# PD_MK2_Connectors.net
KiCad netlist of a schematic drawn in Altium Designer
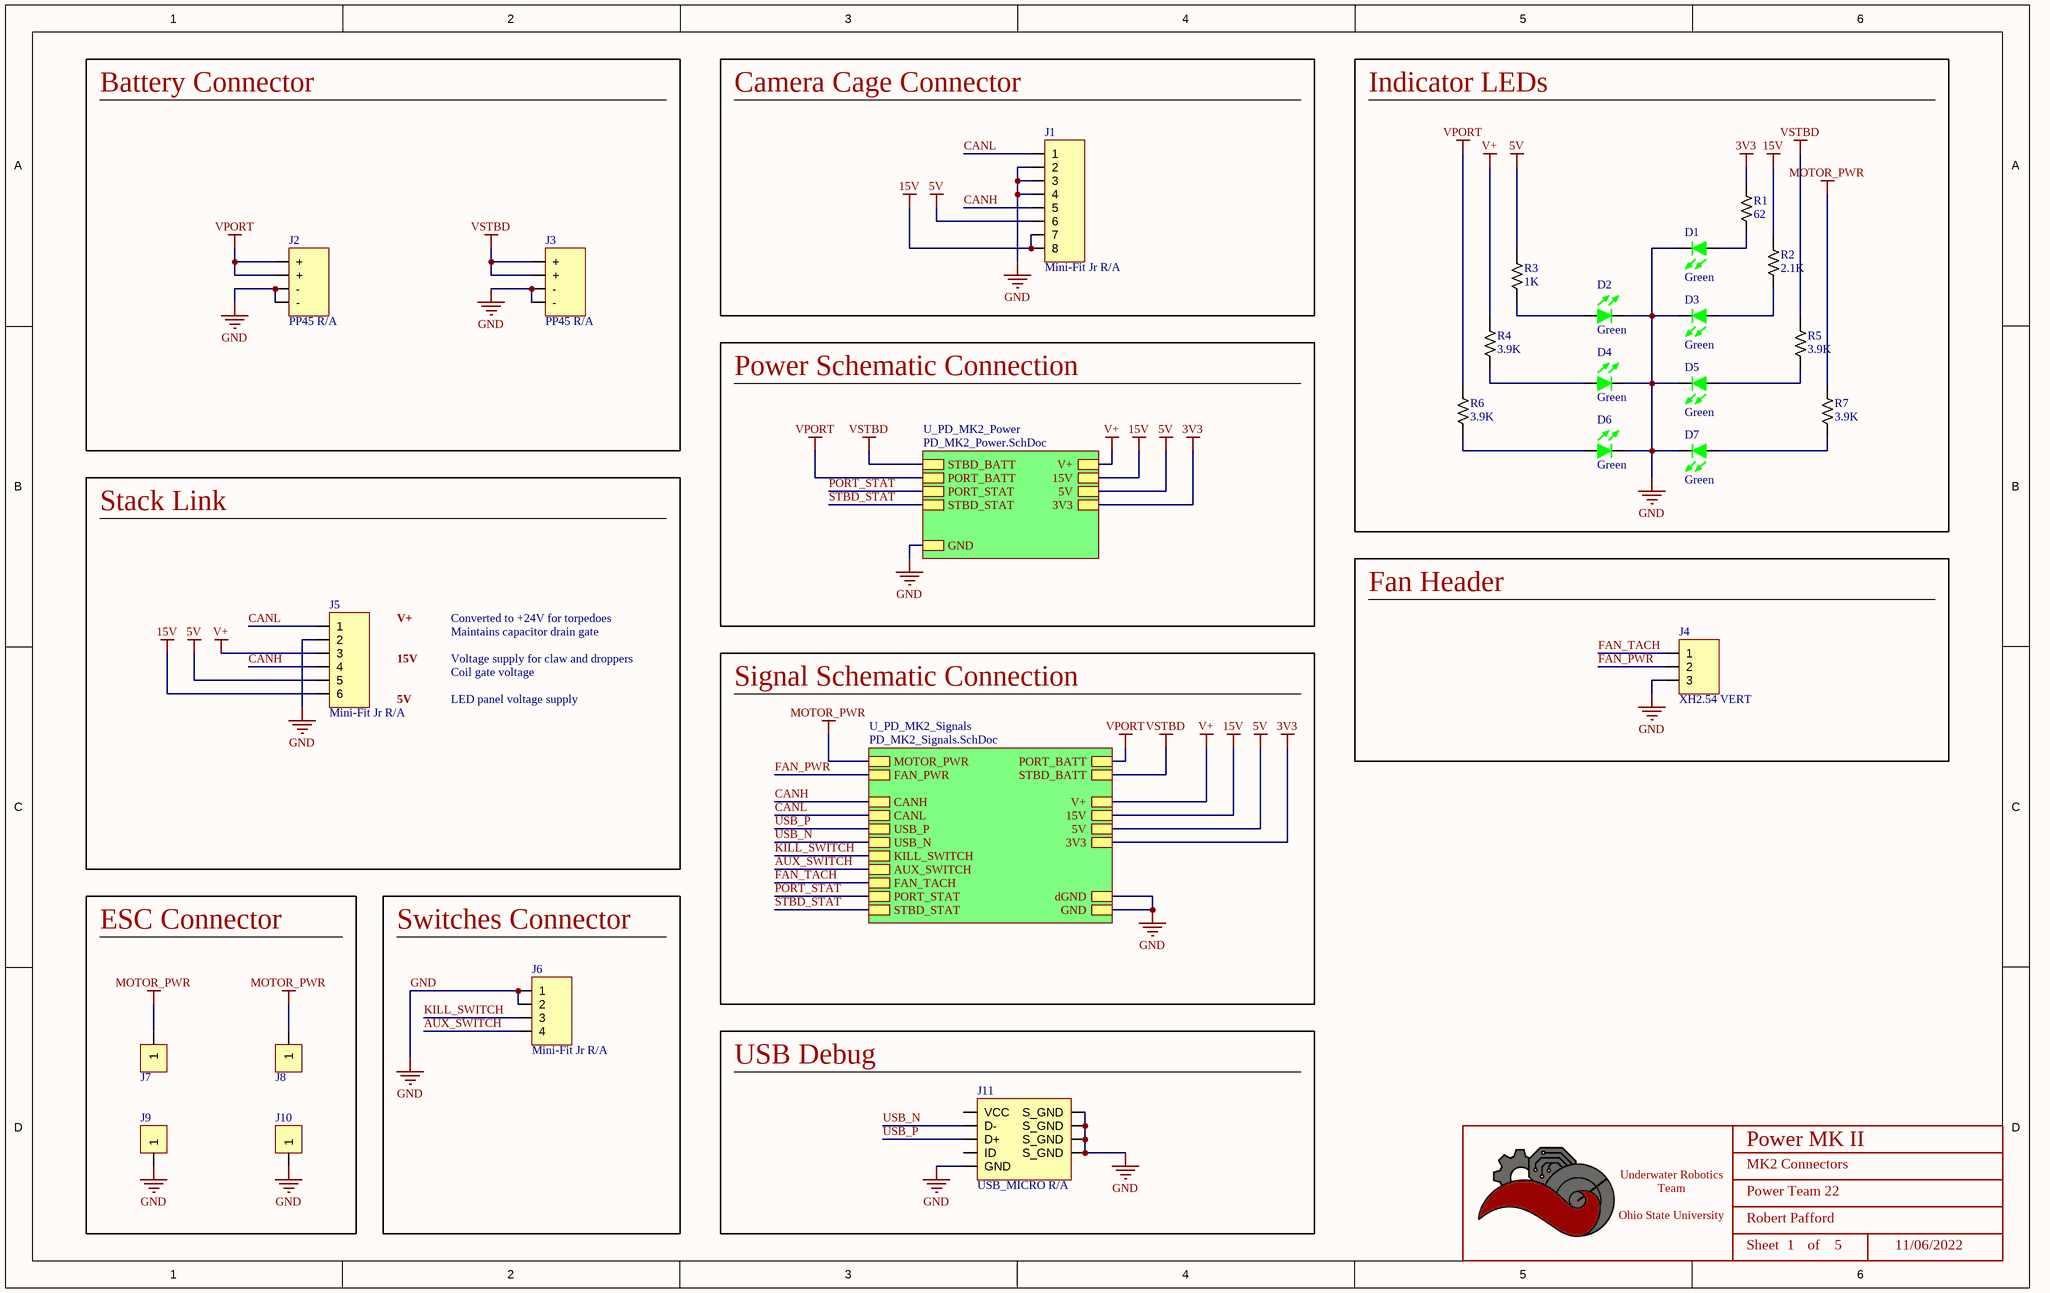
[diagram p0: PD_MK2_Connectors.SchDoc]

(export (version "E")
  (design (tool "Eeschema 10.0.6"))
  (components
    (comp (ref "D1")
      (value "IN-S63AT5G")
      (footprint "LED_0603")
      (description "LED Green Vf= 3V If = 0.005A\r\nIN-S63AT5G")
      (fields (field (name "COLOR") "Green") (field (name "MADE BY") "Robert Pafford"))
      (libsource (lib "Diodes") (part "LED_Green_0603_3V"))
    )
    (comp (ref "D2")
      (value "IN-S63AT5G")
      (footprint "LED_0603")
      (description "LED Green Vf= 3V If = 0.005A\r\nIN-S63AT5G")
      (fields (field (name "COLOR") "Green") (field (name "MADE BY") "Robert Pafford"))
      (libsource (lib "Diodes") (part "LED_Green_0603_3V"))
    )
    (comp (ref "D3")
      (value "IN-S63AT5G")
      (footprint "LED_0603")
      (description "LED Green Vf= 3V If = 0.005A\r\nIN-S63AT5G")
      (fields (field (name "COLOR") "Green") (field (name "MADE BY") "Robert Pafford"))
      (libsource (lib "Diodes") (part "LED_Green_0603_3V"))
    )
    (comp (ref "D4")
      (value "IN-S63AT5G")
      (footprint "LED_0603")
      (description "LED Green Vf= 3V If = 0.005A\r\nIN-S63AT5G")
      (fields (field (name "COLOR") "Green") (field (name "MADE BY") "Robert Pafford"))
      (libsource (lib "Diodes") (part "LED_Green_0603_3V"))
    )
    (comp (ref "D5")
      (value "IN-S63AT5G")
      (footprint "LED_0603")
      (description "LED Green Vf= 3V If = 0.005A\r\nIN-S63AT5G")
      (fields (field (name "COLOR") "Green") (field (name "MADE BY") "Robert Pafford"))
      (libsource (lib "Diodes") (part "LED_Green_0603_3V"))
    )
    (comp (ref "D6")
      (value "IN-S63AT5G")
      (footprint "LED_0603")
      (description "LED Green Vf= 3V If = 0.005A\r\nIN-S63AT5G")
      (fields (field (name "COLOR") "Green") (field (name "MADE BY") "Robert Pafford"))
      (libsource (lib "Diodes") (part "LED_Green_0603_3V"))
    )
    (comp (ref "D7")
      (value "IN-S63AT5G")
      (footprint "LED_0603")
      (description "LED Green Vf= 3V If = 0.005A\r\nIN-S63AT5G")
      (fields (field (name "COLOR") "Green") (field (name "MADE BY") "Robert Pafford"))
      (libsource (lib "Diodes") (part "LED_Green_0603_3V"))
    )
    (comp (ref "J1")
      (value "Mini-Fit Jr R/A")
      (footprint "CONN_MOLEX_MINIFIT JR_8 POS_R/A")
      (description "Molex Minifit Jr. 5569 \r\n8 Pos R/A Natural")
      (fields (field (name "MANUFACTURER") "Molex") (field (name "CREATED BY") "Flip B"))
      (libsource (lib "Connectors") (part "CONN_MOLEX_MINIFIT JR_8POS_R/A"))
    )
    (comp (ref "J2")
      (value "PP45 R/A")
      (footprint "CONN_ANDERSON_PP45_4 POS_R/A")
      (description "Anderson PP45\r\n4 Pos R/A Red/Black")
      (fields (field (name "MANUFACTURER") "Anderson") (field (name "CREATED BY") "Flip B"))
      (libsource (lib "Connectors") (part "CONN_ANDERSON_2x2_R/A"))
    )
    (comp (ref "J3")
      (value "PP45 R/A")
      (footprint "CONN_ANDERSON_PP45_4 POS_R/A")
      (description "Anderson PP45\r\n4 Pos R/A Red/Black")
      (fields (field (name "MANUFACTURER") "Anderson") (field (name "CREATED BY") "Flip B"))
      (libsource (lib "Connectors") (part "CONN_ANDERSON_2x2_R/A"))
    )
    (comp (ref "J4")
      (value "XH2.54 VERT")
      (footprint "CONN_JST_XH254_3POS_VERT")
      (description "JST XH 2.54mm Pitch 3 Pos Vertical")
      (fields (field (name "MANUFACTURER") "JST") (field (name "CREATED BY") "Robert P"))
      (libsource (lib "Connectors") (part "CONN_JST_XH254_3POS_VERT"))
    )
    (comp (ref "J5")
      (value "Mini-Fit Jr R/A")
      (footprint "CONN_MOLEX_MINIFIT JR_6 POS_R/A")
      (description "Molex Minifit Jr. 5569 \r\n6 Pos R/A Natural")
      (fields (field (name "MANUFACTURER") "Molex") (field (name "CREATED BY") "Flip B"))
      (libsource (lib "Connectors") (part "CONN_MOLEX_MINIFIT JR_6POS_R/A"))
    )
    (comp (ref "J6")
      (value "Mini-Fit Jr R/A")
      (footprint "CONN_MOLEX_MINIFIT JR_4 POS_R/A")
      (description "Molex Minifit Jr. 5569 \r\n4 Pos R/A Natural")
      (fields (field (name "MANUFACTURER") "Molex") (field (name "CREATED BY") "Flip B"))
      (libsource (lib "Connectors") (part "CONN_MOLEX_MINIFIT JR_4POS_R/A"))
    )
    (comp (ref "J7")
      (value "Redcube M4 Term 85A")
      (footprint "Redcube M4 Term 85A")
      (fields (field (name "CREATED BY") "Nahtan Ayer"))
      (libsource (lib "Connectors") (part "Redcube M4 Term 85A"))
    )
    (comp (ref "J8")
      (value "Redcube M4 Term 85A")
      (footprint "Redcube M4 Term 85A")
      (fields (field (name "CREATED BY") "Nahtan Ayer"))
      (libsource (lib "Connectors") (part "Redcube M4 Term 85A"))
    )
    (comp (ref "J9")
      (value "Redcube M4 Term 85A")
      (footprint "Redcube M4 Term 85A")
      (fields (field (name "CREATED BY") "Nahtan Ayer"))
      (libsource (lib "") (part "Redcube M4 Term 85A_1"))
    )
    (comp (ref "J10")
      (value "Redcube M4 Term 85A")
      (footprint "Redcube M4 Term 85A")
      (fields (field (name "CREATED BY") "Nahtan Ayer"))
      (libsource (lib "") (part "Redcube M4 Term 85A_1"))
    )
    (comp (ref "J11")
      (value "USB_MICRO R/A")
      (footprint "CONN_MINIUSB")
      (description "Amphenol Micro USB-B\r\nUSB2.0 5 Pin Right Angle SMD")
      (fields (field (name "MANUFACTURER") "Amphenol") (field (name "CREATED BY") "Flip B"))
      (libsource (lib "Connectors") (part "CONN_MICROUSB"))
    )
    (comp (ref "R1")
      (value "62 Ohm 1% 1/4W")
      (footprint "RESISTOR_0603")
      (description "RES SMD 62 OHM 1% 1/4W 0603")
      (fields
        (field (name "TOLERANCE") "+/- 1%")
        (field (name "VALUE  (OHMS)") "62")
        (field (name "MADE BY") "Robert Pafford")
      )
      (libsource (lib "Resistors") (part "RESISTOR_62_0603"))
    )
    (comp (ref "R2")
      (value "2.1k Ohm 5% 1/8W")
      (footprint "RESISTOR_0603")
      (description "RES 2.1k OHM 5% 1/8W 0603")
      (fields
        (field (name "TOLERANCE") "+/- 5%")
        (field (name "VALUE  (OHMS)") "2.1K")
        (field (name "MADE BY") "Robert Pafford")
      )
      (libsource (lib "Resistors") (part "RESISTOR_2.1K_0603"))
    )
    (comp (ref "R3")
      (value "1k Ohm 5% 1/8W")
      (footprint "RESISTOR_0603")
      (description "RES 1k OHM 5% 1/8W 0603")
      (fields
        (field (name "TOLERANCE") "+/- 5%")
        (field (name "VALUE  (OHMS)") "1K")
        (field (name "MADE BY") "Robert Pafford")
      )
      (libsource (lib "Resistors") (part "RESISTOR_1K_0603"))
    )
    (comp (ref "R4")
      (value "3.9k Ohm 5% 1/10W")
      (footprint "RESISTOR_0603")
      (description "RES 3.9k OHM 1% 1/10W 0603")
      (fields
        (field (name "TOLERANCE") "+/- 1%")
        (field (name "VALUE  (OHMS)") "3.9K")
        (field (name "MADE BY") "Robert Pafford")
      )
      (libsource (lib "Resistors") (part "RESISTOR_3.9K_0603"))
    )
    (comp (ref "R5")
      (value "3.9k Ohm 5% 1/10W")
      (footprint "RESISTOR_0603")
      (description "RES 3.9k OHM 1% 1/10W 0603")
      (fields
        (field (name "TOLERANCE") "+/- 1%")
        (field (name "VALUE  (OHMS)") "3.9K")
        (field (name "MADE BY") "Robert Pafford")
      )
      (libsource (lib "Resistors") (part "RESISTOR_3.9K_0603"))
    )
    (comp (ref "R6")
      (value "3.9k Ohm 5% 1/10W")
      (footprint "RESISTOR_0603")
      (description "RES 3.9k OHM 1% 1/10W 0603")
      (fields
        (field (name "TOLERANCE") "+/- 1%")
        (field (name "VALUE  (OHMS)") "3.9K")
        (field (name "MADE BY") "Robert Pafford")
      )
      (libsource (lib "Resistors") (part "RESISTOR_3.9K_0603"))
    )
    (comp (ref "R7")
      (value "3.9k Ohm 5% 1/10W")
      (footprint "RESISTOR_0603")
      (description "RES 3.9k OHM 1% 1/10W 0603")
      (fields
        (field (name "TOLERANCE") "+/- 1%")
        (field (name "VALUE  (OHMS)") "3.9K")
        (field (name "MADE BY") "Robert Pafford")
      )
      (libsource (lib "Resistors") (part "RESISTOR_3.9K_0603"))
    )
  )
  (nets
    (net (code "1") (name "/AUX_SWITCH") (class "Default")
      (node (ref "J6") (pin "4") (pinfunction "4_4") (pintype "passive"))
    )
    (net (code "2") (name "/CANH") (class "Default")
      (node (ref "J1") (pin "5") (pinfunction "5_5") (pintype "passive"))
      (node (ref "J5") (pin "4") (pinfunction "4_4") (pintype "passive"))
    )
    (net (code "3") (name "/CANL") (class "Default")
      (node (ref "J1") (pin "1") (pinfunction "1_1") (pintype "passive"))
      (node (ref "J5") (pin "1") (pinfunction "1_1") (pintype "passive"))
    )
    (net (code "4") (name "/FAN_PWR") (class "Default")
      (node (ref "J4") (pin "2") (pinfunction "2_2") (pintype "passive"))
    )
    (net (code "5") (name "/FAN_TACH") (class "Default")
      (node (ref "J4") (pin "1") (pinfunction "1_1") (pintype "passive"))
    )
    (net (code "6") (name "/KILL_SWITCH") (class "Default")
      (node (ref "J6") (pin "3") (pinfunction "3_3") (pintype "passive"))
    )
    (net (code "9") (name "/USB_N") (class "Default")
      (node (ref "J11") (pin "2") (pinfunction "D-_2") (pintype "passive"))
    )
    (net (code "10") (name "/USB_P") (class "Default")
      (node (ref "J11") (pin "3") (pinfunction "D+_3") (pintype "passive"))
    )
    (net (code "11") (name "3V3") (class "Default")
      (node (ref "R1") (pin "1") (pinfunction "1_1") (pintype "passive"))
    )
    (net (code "12") (name "5V") (class "Default")
      (node (ref "J1") (pin "6") (pinfunction "6_6") (pintype "passive"))
      (node (ref "J5") (pin "5") (pinfunction "5_5") (pintype "passive"))
      (node (ref "R3") (pin "1") (pinfunction "1_1") (pintype "passive"))
    )
    (net (code "13") (name "15V") (class "Default")
      (node (ref "J1") (pin "7") (pinfunction "7_7") (pintype "passive"))
      (node (ref "J1") (pin "8") (pinfunction "8_8") (pintype "passive"))
      (node (ref "J5") (pin "6") (pinfunction "6_6") (pintype "passive"))
      (node (ref "R2") (pin "1") (pinfunction "1_1") (pintype "passive"))
    )
    (net (code "14") (name "GND") (class "Default")
      (node (ref "D1") (pin "2") (pinfunction "2_2") (pintype "passive"))
      (node (ref "D2") (pin "2") (pinfunction "2_2") (pintype "passive"))
      (node (ref "D3") (pin "2") (pinfunction "2_2") (pintype "passive"))
      (node (ref "D4") (pin "2") (pinfunction "2_2") (pintype "passive"))
      (node (ref "D5") (pin "2") (pinfunction "2_2") (pintype "passive"))
      (node (ref "D6") (pin "2") (pinfunction "2_2") (pintype "passive"))
      (node (ref "D7") (pin "2") (pinfunction "2_2") (pintype "passive"))
      (node (ref "J1") (pin "2") (pinfunction "2_2") (pintype "passive"))
      (node (ref "J1") (pin "3") (pinfunction "3_3") (pintype "passive"))
      (node (ref "J1") (pin "4") (pinfunction "4_4") (pintype "passive"))
      (node (ref "J10") (pin "1") (pinfunction "1_1") (pintype "passive"))
      (node (ref "J11") (pin "5") (pinfunction "GND_5") (pintype "passive"))
      (node (ref "J11") (pin "6") (pinfunction "S_GND_6") (pintype "passive"))
      (node (ref "J11") (pin "7") (pinfunction "S_GND_7") (pintype "passive"))
      (node (ref "J11") (pin "8") (pinfunction "S_GND_8") (pintype "passive"))
      (node (ref "J11") (pin "9") (pinfunction "S_GND_9") (pintype "passive"))
      (node (ref "J2") (pin "3") (pinfunction "-_3") (pintype "passive"))
      (node (ref "J2") (pin "4") (pinfunction "-_4") (pintype "passive"))
      (node (ref "J3") (pin "3") (pinfunction "-_3") (pintype "passive"))
      (node (ref "J3") (pin "4") (pinfunction "-_4") (pintype "passive"))
      (node (ref "J4") (pin "3") (pinfunction "3_3") (pintype "passive"))
      (node (ref "J5") (pin "2") (pinfunction "2_2") (pintype "passive"))
      (node (ref "J6") (pin "1") (pinfunction "1_1") (pintype "passive"))
      (node (ref "J6") (pin "2") (pinfunction "2_2") (pintype "passive"))
      (node (ref "J9") (pin "1") (pinfunction "1_1") (pintype "passive"))
    )
    (net (code "15") (name "MOTOR_PWR") (class "Default")
      (node (ref "J7") (pin "1") (pinfunction "1_1") (pintype "passive"))
      (node (ref "J8") (pin "1") (pinfunction "1_1") (pintype "passive"))
      (node (ref "R7") (pin "1") (pinfunction "1_1") (pintype "passive"))
    )
    (net (code "16") (name "Net-(D1-Pad1)") (class "Default")
      (node (ref "D1") (pin "1") (pinfunction "1_1") (pintype "passive"))
      (node (ref "R1") (pin "2") (pinfunction "2_2") (pintype "passive"))
    )
    (net (code "17") (name "Net-(D2-Pad1)") (class "Default")
      (node (ref "D2") (pin "1") (pinfunction "1_1") (pintype "passive"))
      (node (ref "R3") (pin "2") (pinfunction "2_2") (pintype "passive"))
    )
    (net (code "18") (name "Net-(D3-Pad1)") (class "Default")
      (node (ref "D3") (pin "1") (pinfunction "1_1") (pintype "passive"))
      (node (ref "R2") (pin "2") (pinfunction "2_2") (pintype "passive"))
    )
    (net (code "19") (name "Net-(D4-Pad1)") (class "Default")
      (node (ref "D4") (pin "1") (pinfunction "1_1") (pintype "passive"))
      (node (ref "R4") (pin "2") (pinfunction "2_2") (pintype "passive"))
    )
    (net (code "20") (name "Net-(D5-Pad1)") (class "Default")
      (node (ref "D5") (pin "1") (pinfunction "1_1") (pintype "passive"))
      (node (ref "R5") (pin "2") (pinfunction "2_2") (pintype "passive"))
    )
    (net (code "21") (name "Net-(D6-Pad1)") (class "Default")
      (node (ref "D6") (pin "1") (pinfunction "1_1") (pintype "passive"))
      (node (ref "R6") (pin "2") (pinfunction "2_2") (pintype "passive"))
    )
    (net (code "22") (name "Net-(D7-Pad1)") (class "Default")
      (node (ref "D7") (pin "1") (pinfunction "1_1") (pintype "passive"))
      (node (ref "R7") (pin "2") (pinfunction "2_2") (pintype "passive"))
    )
    (net (code "23") (name "V+") (class "Default")
      (node (ref "J5") (pin "3") (pinfunction "3_3") (pintype "passive"))
      (node (ref "R4") (pin "1") (pinfunction "1_1") (pintype "passive"))
    )
    (net (code "24") (name "VPORT") (class "Default")
      (node (ref "J2") (pin "1") (pinfunction "+_1") (pintype "passive"))
      (node (ref "J2") (pin "2") (pinfunction "+_2") (pintype "passive"))
      (node (ref "R6") (pin "1") (pinfunction "1_1") (pintype "passive"))
    )
    (net (code "25") (name "VSTBD") (class "Default")
      (node (ref "J3") (pin "1") (pinfunction "+_1") (pintype "passive"))
      (node (ref "J3") (pin "2") (pinfunction "+_2") (pintype "passive"))
      (node (ref "R5") (pin "1") (pinfunction "1_1") (pintype "passive"))
    )
    (net (code "26") (name "unconnected-(J11-ID-Pad4)") (class "Default")
      (node (ref "J11") (pin "4") (pinfunction "ID_4") (pintype "passive"))
    )
    (net (code "27") (name "unconnected-(J11-VCC-Pad1)") (class "Default")
      (node (ref "J11") (pin "1") (pinfunction "VCC_1") (pintype "passive"))
    )
  )
)
